# Snippet_of_MS9333_Power.net
KiCad netlist of a schematic drawn in Altium Designer
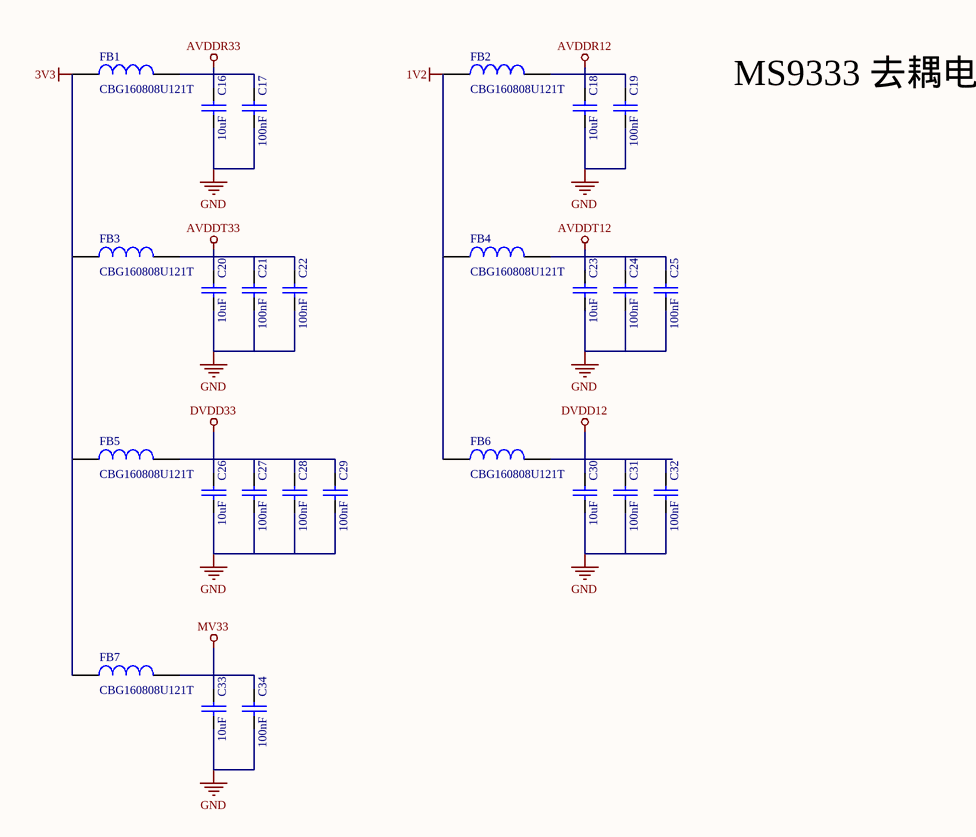
[diagram p0: Snippet of MS9333_Power.SchDoc]

(export (version "E")
  (design (tool "Eeschema 10.0.6"))
  (components
    (comp (ref "C16")
      (value "10uF")
      (footprint "C_0603")
      (description "贴片电容")
      (libsource (lib "IntLib-Passive") (part "Cap_Chip"))
    )
    (comp (ref "C17")
      (value "100nF")
      (footprint "C_0402")
      (description "贴片电容")
      (libsource (lib "IntLib-Passive") (part "Cap_Chip"))
    )
    (comp (ref "C18")
      (value "10uF")
      (footprint "C_0603")
      (description "贴片电容")
      (libsource (lib "IntLib-Passive") (part "Cap_Chip"))
    )
    (comp (ref "C19")
      (value "100nF")
      (footprint "C_0402")
      (description "贴片电容")
      (libsource (lib "IntLib-Passive") (part "Cap_Chip"))
    )
    (comp (ref "C20")
      (value "10uF")
      (footprint "C_0603")
      (description "贴片电容")
      (libsource (lib "IntLib-Passive") (part "Cap_Chip"))
    )
    (comp (ref "C21")
      (value "100nF")
      (footprint "C_0402")
      (description "贴片电容")
      (libsource (lib "IntLib-Passive") (part "Cap_Chip"))
    )
    (comp (ref "C22")
      (value "100nF")
      (footprint "C_0402")
      (description "贴片电容")
      (libsource (lib "IntLib-Passive") (part "Cap_Chip"))
    )
    (comp (ref "C23")
      (value "10uF")
      (footprint "C_0603")
      (description "贴片电容")
      (libsource (lib "IntLib-Passive") (part "Cap_Chip"))
    )
    (comp (ref "C24")
      (value "100nF")
      (footprint "C_0402")
      (description "贴片电容")
      (libsource (lib "IntLib-Passive") (part "Cap_Chip"))
    )
    (comp (ref "C25")
      (value "100nF")
      (footprint "C_0402")
      (description "贴片电容")
      (libsource (lib "IntLib-Passive") (part "Cap_Chip"))
    )
    (comp (ref "C26")
      (value "10uF")
      (footprint "C_0603")
      (description "贴片电容")
      (libsource (lib "IntLib-Passive") (part "Cap_Chip"))
    )
    (comp (ref "C27")
      (value "100nF")
      (footprint "C_0402")
      (description "贴片电容")
      (libsource (lib "IntLib-Passive") (part "Cap_Chip"))
    )
    (comp (ref "C28")
      (value "100nF")
      (footprint "C_0402")
      (description "贴片电容")
      (libsource (lib "IntLib-Passive") (part "Cap_Chip"))
    )
    (comp (ref "C29")
      (value "100nF")
      (footprint "C_0402")
      (description "贴片电容")
      (libsource (lib "IntLib-Passive") (part "Cap_Chip"))
    )
    (comp (ref "C30")
      (value "10uF")
      (footprint "C_0603")
      (description "贴片电容")
      (libsource (lib "IntLib-Passive") (part "Cap_Chip"))
    )
    (comp (ref "C31")
      (value "100nF")
      (footprint "C_0402")
      (description "贴片电容")
      (libsource (lib "IntLib-Passive") (part "Cap_Chip"))
    )
    (comp (ref "C32")
      (value "100nF")
      (footprint "C_0402")
      (description "贴片电容")
      (libsource (lib "IntLib-Passive") (part "Cap_Chip"))
    )
    (comp (ref "C33")
      (value "10uF")
      (footprint "C_0603")
      (description "贴片电容")
      (libsource (lib "IntLib-Passive") (part "Cap_Chip"))
    )
    (comp (ref "C34")
      (value "100nF")
      (footprint "C_0402")
      (description "贴片电容")
      (libsource (lib "IntLib-Passive") (part "Cap_Chip"))
    )
    (comp (ref "FB1")
      (value "CBG160808U121T")
      (footprint "0603L")
      (description "120R 100Mhz")
      (libsource (lib "Inductance") (part "FB"))
    )
    (comp (ref "FB2")
      (value "CBG160808U121T")
      (footprint "0603L")
      (description "120R 100Mhz")
      (libsource (lib "Inductance") (part "FB"))
    )
    (comp (ref "FB3")
      (value "CBG160808U121T")
      (footprint "0603L")
      (description "120R 100Mhz")
      (libsource (lib "Inductance") (part "FB"))
    )
    (comp (ref "FB4")
      (value "CBG160808U121T")
      (footprint "0603L")
      (description "120R 100Mhz")
      (libsource (lib "Inductance") (part "FB"))
    )
    (comp (ref "FB5")
      (value "CBG160808U121T")
      (footprint "0603L")
      (description "120R 100Mhz")
      (libsource (lib "Inductance") (part "FB"))
    )
    (comp (ref "FB6")
      (value "CBG160808U121T")
      (footprint "0603L")
      (description "120R 100Mhz")
      (libsource (lib "Inductance") (part "FB"))
    )
    (comp (ref "FB7")
      (value "CBG160808U121T")
      (footprint "0603L")
      (description "120R 100Mhz")
      (libsource (lib "Inductance") (part "FB"))
    )
  )
  (nets
    (net (code "1") (name "1V2") (class "Default")
      (node (ref "FB2") (pin "1") (pinfunction "1_1") (pintype "passive"))
      (node (ref "FB4") (pin "1") (pinfunction "1_1") (pintype "passive"))
      (node (ref "FB6") (pin "1") (pinfunction "1_1") (pintype "passive"))
    )
    (net (code "2") (name "3V3") (class "Default")
      (node (ref "FB1") (pin "1") (pinfunction "1_1") (pintype "passive"))
      (node (ref "FB3") (pin "1") (pinfunction "1_1") (pintype "passive"))
      (node (ref "FB5") (pin "1") (pinfunction "1_1") (pintype "passive"))
      (node (ref "FB7") (pin "1") (pinfunction "1_1") (pintype "passive"))
    )
    (net (code "3") (name "AVDDR12") (class "Default")
      (node (ref "C18") (pin "1") (pinfunction "1_1") (pintype "passive"))
      (node (ref "C19") (pin "1") (pinfunction "1_1") (pintype "passive"))
      (node (ref "FB2") (pin "2") (pinfunction "2_2") (pintype "passive"))
    )
    (net (code "4") (name "AVDDR33") (class "Default")
      (node (ref "C16") (pin "1") (pinfunction "1_1") (pintype "passive"))
      (node (ref "C17") (pin "1") (pinfunction "1_1") (pintype "passive"))
      (node (ref "FB1") (pin "2") (pinfunction "2_2") (pintype "passive"))
    )
    (net (code "5") (name "AVDDT12") (class "Default")
      (node (ref "C23") (pin "1") (pinfunction "1_1") (pintype "passive"))
      (node (ref "C24") (pin "1") (pinfunction "1_1") (pintype "passive"))
      (node (ref "C25") (pin "1") (pinfunction "1_1") (pintype "passive"))
      (node (ref "FB4") (pin "2") (pinfunction "2_2") (pintype "passive"))
    )
    (net (code "6") (name "AVDDT33") (class "Default")
      (node (ref "C20") (pin "1") (pinfunction "1_1") (pintype "passive"))
      (node (ref "C21") (pin "1") (pinfunction "1_1") (pintype "passive"))
      (node (ref "C22") (pin "1") (pinfunction "1_1") (pintype "passive"))
      (node (ref "FB3") (pin "2") (pinfunction "2_2") (pintype "passive"))
    )
    (net (code "7") (name "DVDD12") (class "Default")
      (node (ref "C30") (pin "1") (pinfunction "1_1") (pintype "passive"))
      (node (ref "C31") (pin "1") (pinfunction "1_1") (pintype "passive"))
      (node (ref "C32") (pin "1") (pinfunction "1_1") (pintype "passive"))
      (node (ref "FB6") (pin "2") (pinfunction "2_2") (pintype "passive"))
    )
    (net (code "8") (name "DVDD33") (class "Default")
      (node (ref "C26") (pin "1") (pinfunction "1_1") (pintype "passive"))
      (node (ref "C27") (pin "1") (pinfunction "1_1") (pintype "passive"))
      (node (ref "C28") (pin "1") (pinfunction "1_1") (pintype "passive"))
      (node (ref "C29") (pin "1") (pinfunction "1_1") (pintype "passive"))
      (node (ref "FB5") (pin "2") (pinfunction "2_2") (pintype "passive"))
    )
    (net (code "9") (name "GND") (class "Default")
      (node (ref "C16") (pin "2") (pinfunction "2_2") (pintype "passive"))
      (node (ref "C17") (pin "2") (pinfunction "2_2") (pintype "passive"))
      (node (ref "C18") (pin "2") (pinfunction "2_2") (pintype "passive"))
      (node (ref "C19") (pin "2") (pinfunction "2_2") (pintype "passive"))
      (node (ref "C20") (pin "2") (pinfunction "2_2") (pintype "passive"))
      (node (ref "C21") (pin "2") (pinfunction "2_2") (pintype "passive"))
      (node (ref "C22") (pin "2") (pinfunction "2_2") (pintype "passive"))
      (node (ref "C23") (pin "2") (pinfunction "2_2") (pintype "passive"))
      (node (ref "C24") (pin "2") (pinfunction "2_2") (pintype "passive"))
      (node (ref "C25") (pin "2") (pinfunction "2_2") (pintype "passive"))
      (node (ref "C26") (pin "2") (pinfunction "2_2") (pintype "passive"))
      (node (ref "C27") (pin "2") (pinfunction "2_2") (pintype "passive"))
      (node (ref "C28") (pin "2") (pinfunction "2_2") (pintype "passive"))
      (node (ref "C29") (pin "2") (pinfunction "2_2") (pintype "passive"))
      (node (ref "C30") (pin "2") (pinfunction "2_2") (pintype "passive"))
      (node (ref "C31") (pin "2") (pinfunction "2_2") (pintype "passive"))
      (node (ref "C32") (pin "2") (pinfunction "2_2") (pintype "passive"))
      (node (ref "C33") (pin "2") (pinfunction "2_2") (pintype "passive"))
      (node (ref "C34") (pin "2") (pinfunction "2_2") (pintype "passive"))
    )
    (net (code "10") (name "MV33") (class "Default")
      (node (ref "C33") (pin "1") (pinfunction "1_1") (pintype "passive"))
      (node (ref "C34") (pin "1") (pinfunction "1_1") (pintype "passive"))
      (node (ref "FB7") (pin "2") (pinfunction "2_2") (pintype "passive"))
    )
  )
)
